# Deej.net
KiCad netlist of a schematic drawn in Altium Designer
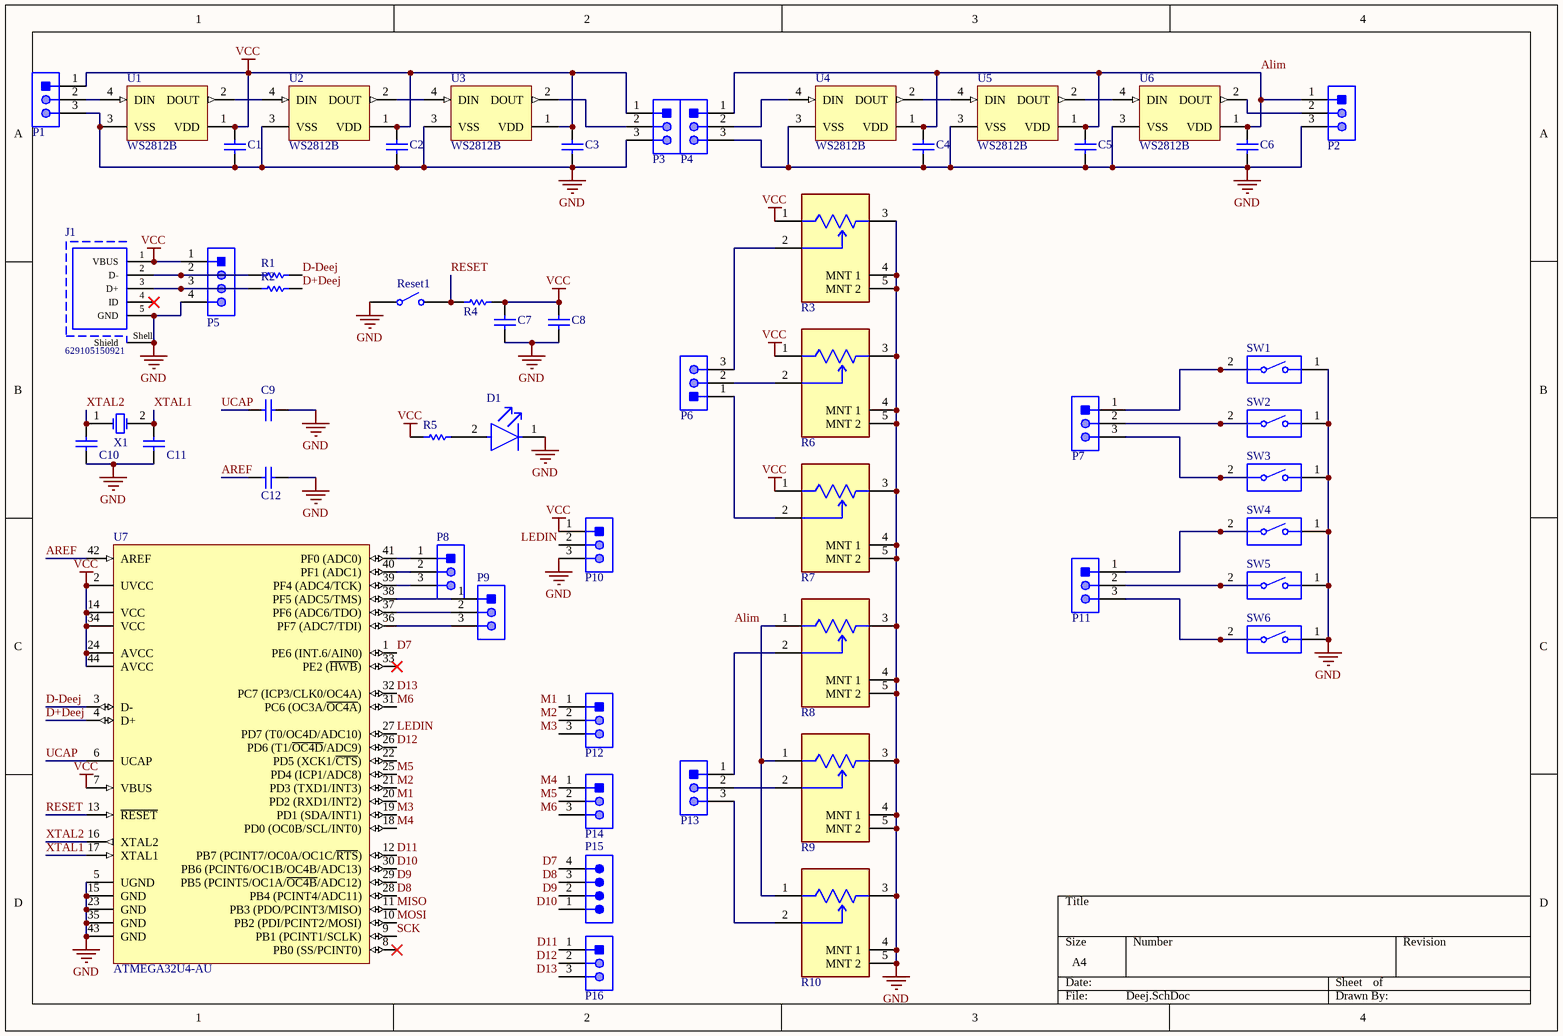
[diagram p0: Deej.SchDoc]

(export (version "E")
  (design (tool "Eeschema 10.0.6"))
  (components
    (comp (ref "C1")
      (value "GRM31C5C1E104JA01L")
      (footprint "CAPC3216X180X55LL20T25")
      (description "Chip Capacitor, 100 nF, +/- 5%, 25 V, -55 to 125 degC, 1206 (3216 Metric), RoHS, Tape and Reel")
      (fields (field (name "MANUFACTURER") "Murata"))
      (libsource (lib "Altium Content Vault") (part "CAP-NP-2"))
    )
    (comp (ref "C2")
      (value "GRM31C5C1E104JA01L")
      (footprint "CAPC3216X180X55LL20T25")
      (description "Chip Capacitor, 100 nF, +/- 5%, 25 V, -55 to 125 degC, 1206 (3216 Metric), RoHS, Tape and Reel")
      (fields (field (name "MANUFACTURER") "Murata"))
      (libsource (lib "Altium Content Vault") (part "CAP-NP-2"))
    )
    (comp (ref "C3")
      (value "GRM31C5C1E104JA01L")
      (footprint "CAPC3216X180X55LL20T25")
      (description "Chip Capacitor, 100 nF, +/- 5%, 25 V, -55 to 125 degC, 1206 (3216 Metric), RoHS, Tape and Reel")
      (fields (field (name "MANUFACTURER") "Murata"))
      (libsource (lib "Altium Content Vault") (part "CAP-NP-2"))
    )
    (comp (ref "C4")
      (value "GRM31C5C1E104JA01L")
      (footprint "CAPC3216X180X55LL20T25")
      (description "Chip Capacitor, 100 nF, +/- 5%, 25 V, -55 to 125 degC, 1206 (3216 Metric), RoHS, Tape and Reel")
      (fields (field (name "MANUFACTURER") "Murata"))
      (libsource (lib "Altium Content Vault") (part "CAP-NP-2"))
    )
    (comp (ref "C5")
      (value "GRM31C5C1E104JA01L")
      (footprint "CAPC3216X180X55LL20T25")
      (description "Chip Capacitor, 100 nF, +/- 5%, 25 V, -55 to 125 degC, 1206 (3216 Metric), RoHS, Tape and Reel")
      (fields (field (name "MANUFACTURER") "Murata"))
      (libsource (lib "Altium Content Vault") (part "CAP-NP-2"))
    )
    (comp (ref "C6")
      (value "GRM31C5C1E104JA01L")
      (footprint "CAPC3216X180X55LL20T25")
      (description "Chip Capacitor, 100 nF, +/- 5%, 25 V, -55 to 125 degC, 1206 (3216 Metric), RoHS, Tape and Reel")
      (fields (field (name "MANUFACTURER") "Murata"))
      (libsource (lib "Altium Content Vault") (part "CAP-NP-2"))
    )
    (comp (ref "C7")
      (value "GRM31C5C1E104JA01L")
      (footprint "CAPC3216X180X55LL20T25")
      (description "Chip Capacitor, 100 nF, +/- 5%, 25 V, -55 to 125 degC, 1206 (3216 Metric), RoHS, Tape and Reel")
      (fields (field (name "MANUFACTURER") "Murata"))
      (libsource (lib "Altium Content Vault") (part "CAP-NP-2"))
    )
    (comp (ref "C8")
      (value "GRM31C5C1E104JA01L")
      (footprint "CAPC3216X180X55LL20T25")
      (description "Chip Capacitor, 100 nF, +/- 5%, 25 V, -55 to 125 degC, 1206 (3216 Metric), RoHS, Tape and Reel")
      (fields (field (name "MANUFACTURER") "Murata"))
      (libsource (lib "Altium Content Vault") (part "CAP-NP-2"))
    )
    (comp (ref "C9")
      (value "C1206C105K3RACTU")
      (footprint "CAPC3216X180X50ML20T25")
      (description "Chip Capacitor, 1 uF, +/- 10%, 25 V, -55 to 125 degC, 1206 (3216 Metric), RoHS, Tape and Reel")
      (fields (field (name "MANUFACTURER") "Kemet") (field (name "TOLERANCE") "10%"))
      (libsource (lib "Altium Content Vault") (part "CAP-NP-2"))
    )
    (comp (ref "C10")
      (value "CAP 22pF 50V 1206(3216)")
      (footprint "CAPC1206(3216)100_N")
      (description "CAP 22nF 50V ±5% 1206 (3216 Metric) Thickness 1mm SMD")
      (fields (field (name "TOLERANCE") "Â±5%"))
      (libsource (lib "Altium Content Vault") (part "CAP"))
    )
    (comp (ref "C11")
      (value "CAP 22 pF 50V 1206(3216)")
      (footprint "CAPC1206(3216)100_N")
      (description "CAP 22nF 50V ±5% 1206 (3216 Metric) Thickness 1mm SMD")
      (fields (field (name "TOLERANCE") "Â±5%"))
      (libsource (lib "Altium Content Vault") (part "CAP"))
    )
    (comp (ref "C12")
      (value "GRM31C5C1E104JA01L")
      (footprint "CAPC3216X180X55LL20T25")
      (description "Chip Capacitor, 100 nF, +/- 5%, 25 V, -55 to 125 degC, 1206 (3216 Metric), RoHS, Tape and Reel")
      (fields (field (name "MANUFACTURER") "Murata"))
      (libsource (lib "Altium Content Vault") (part "CAP-NP-2"))
    )
    (comp (ref "D1")
      (value "APTD3216CGCK")
      (footprint "FP-APTD3216CGCK-MFG")
      (description "LED GREEN CLEAR 2SMD")
      (libsource (lib "Altium Content Vault") (part "8706943c75ba83719d021d2fdc84c58"))
    )
    (comp (ref "J1")
      (value "629105150921")
      (footprint "629105150921")
      (description "Micro USB 2.0 Type AB Receptacle WR-COM, Horizontal, SMT")
      (fields (field (name "MANUFACTURER") "Wurth Elektronik") (field (name "PUBLISHER") "WurthElektronik"))
      (libsource (lib "Altium Content Vault") (part "WE-USB-5-1SHLD"))
    )
    (comp (ref "P1")
      (value "22-28-4033")
      (footprint "MOLX-22-28-4033_V")
      (description "Male Header, Pitch 2.54 mm, 1 x 3 Position, Height 8.38 mm, Tail Length 3.18 mm, RoHS, Bulk")
      (fields (field (name "MANUFACTURER") "Molex"))
      (libsource (lib "") (part "CN-1P-M-R3_2"))
    )
    (comp (ref "P2")
      (value "22-28-4033")
      (footprint "MOLX-22-28-4033_V")
      (description "Male Header, Pitch 2.54 mm, 1 x 3 Position, Height 8.38 mm, Tail Length 3.18 mm, RoHS, Bulk")
      (fields (field (name "MANUFACTURER") "Molex"))
      (libsource (lib "Altium Content Vault") (part "CN-1P-M-R3"))
    )
    (comp (ref "P3")
      (value "22-28-4033")
      (footprint "MOLX-22-28-4033_V")
      (description "Male Header, Pitch 2.54 mm, 1 x 3 Position, Height 8.38 mm, Tail Length 3.18 mm, RoHS, Bulk")
      (fields (field (name "MANUFACTURER") "Molex"))
      (libsource (lib "Altium Content Vault") (part "CN-1P-M-R3"))
    )
    (comp (ref "P4")
      (value "22-28-4033")
      (footprint "MOLX-22-28-4033_V")
      (description "Male Header, Pitch 2.54 mm, 1 x 3 Position, Height 8.38 mm, Tail Length 3.18 mm, RoHS, Bulk")
      (fields (field (name "MANUFACTURER") "Molex"))
      (libsource (lib "") (part "CN-1P-M-R3_2"))
    )
    (comp (ref "P5")
      (value "61300411121")
      (footprint "61300411121")
      (description "THT Vertical Pin Header WR-PHD, Pitch 2.54 mm, Single Row, 4 pins")
      (fields (field (name "MANUFACTURER") "Wurth Elektronik") (field (name "PUBLISHER") "WurthElektronik"))
      (libsource (lib "Altium Content Vault") (part "WE-CN-1P-M-R4"))
    )
    (comp (ref "P6")
      (value "22-28-4033")
      (footprint "MOLX-22-28-4033_V")
      (description "Male Header, Pitch 2.54 mm, 1 x 3 Position, Height 8.38 mm, Tail Length 3.18 mm, RoHS, Bulk")
      (fields (field (name "MANUFACTURER") "Molex"))
      (libsource (lib "") (part "CN-1P-M-R3_1"))
    )
    (comp (ref "P7")
      (value "22-28-4033")
      (footprint "MOLX-22-28-4033_V")
      (description "Male Header, Pitch 2.54 mm, 1 x 3 Position, Height 8.38 mm, Tail Length 3.18 mm, RoHS, Bulk")
      (fields (field (name "MANUFACTURER") "Molex"))
      (libsource (lib "") (part "CN-1P-M-R3_2"))
    )
    (comp (ref "P8")
      (value "22-28-4033")
      (footprint "MOLX-22-28-4033_V")
      (description "Male Header, Pitch 2.54 mm, 1 x 3 Position, Height 8.38 mm, Tail Length 3.18 mm, RoHS, Bulk")
      (fields (field (name "MANUFACTURER") "Molex"))
      (libsource (lib "Altium Content Vault") (part "CN-1P-M-R3"))
    )
    (comp (ref "P9")
      (value "22-28-4033")
      (footprint "MOLX-22-28-4033_V")
      (description "Male Header, Pitch 2.54 mm, 1 x 3 Position, Height 8.38 mm, Tail Length 3.18 mm, RoHS, Bulk")
      (fields (field (name "MANUFACTURER") "Molex"))
      (libsource (lib "Altium Content Vault") (part "CN-1P-M-R3"))
    )
    (comp (ref "P10")
      (value "22-28-4033")
      (footprint "MOLX-22-28-4033_V")
      (description "Male Header, Pitch 2.54 mm, 1 x 3 Position, Height 8.38 mm, Tail Length 3.18 mm, RoHS, Bulk")
      (fields (field (name "MANUFACTURER") "Molex"))
      (libsource (lib "Altium Content Vault") (part "CN-1P-M-R3"))
    )
    (comp (ref "P11")
      (value "22-28-4033")
      (footprint "MOLX-22-28-4033_V")
      (description "Male Header, Pitch 2.54 mm, 1 x 3 Position, Height 8.38 mm, Tail Length 3.18 mm, RoHS, Bulk")
      (fields (field (name "MANUFACTURER") "Molex"))
      (libsource (lib "") (part "CN-1P-M-R3_2"))
    )
    (comp (ref "P12")
      (value "22-28-4033")
      (footprint "MOLX-22-28-4033_V")
      (description "Male Header, Pitch 2.54 mm, 1 x 3 Position, Height 8.38 mm, Tail Length 3.18 mm, RoHS, Bulk")
      (fields (field (name "MANUFACTURER") "Molex"))
      (libsource (lib "Altium Content Vault") (part "CN-1P-M-R3"))
    )
    (comp (ref "P13")
      (value "22-28-4033")
      (footprint "MOLX-22-28-4033_V")
      (description "Male Header, Pitch 2.54 mm, 1 x 3 Position, Height 8.38 mm, Tail Length 3.18 mm, RoHS, Bulk")
      (fields (field (name "MANUFACTURER") "Molex"))
      (libsource (lib "") (part "CN-1P-M-R3_2"))
    )
    (comp (ref "P14")
      (value "22-28-4033")
      (footprint "MOLX-22-28-4033_V")
      (description "Male Header, Pitch 2.54 mm, 1 x 3 Position, Height 8.38 mm, Tail Length 3.18 mm, RoHS, Bulk")
      (fields (field (name "MANUFACTURER") "Molex"))
      (libsource (lib "Altium Content Vault") (part "CN-1P-M-R3"))
    )
    (comp (ref "P15")
      (value "TSW-104-08-T-S")
      (footprint "SMTC-TSW-104-08-X-S")
      (description "0.025\" SQ Post Header, Through-hole, Vertical, -55 to 105 degC, 2.54 mm Pitch, 4-Pin, Male, RoHS")
      (fields (field (name "MANUFACTURER") "Samtec"))
      (libsource (lib "Altium Content Vault") (part "SMTC-TSW-104-08-X-S"))
    )
    (comp (ref "P16")
      (value "22-28-4033")
      (footprint "MOLX-22-28-4033_V")
      (description "Male Header, Pitch 2.54 mm, 1 x 3 Position, Height 8.38 mm, Tail Length 3.18 mm, RoHS, Bulk")
      (fields (field (name "MANUFACTURER") "Molex"))
      (libsource (lib "Altium Content Vault") (part "CN-1P-M-R3"))
    )
    (comp (ref "R1")
      (value "ERJ-8GEYJ220V")
      (footprint "RESC3216X70X50NL05T20")
      (fields (field (name "MANUFACTURER") "Panasonic"))
      (libsource (lib "Altium Content Vault") (part "RES"))
    )
    (comp (ref "R2")
      (value "ERJ-8GEYJ220V")
      (footprint "RESC3216X70X50NL05T20")
      (fields (field (name "MANUFACTURER") "Panasonic"))
      (libsource (lib "Altium Content Vault") (part "RES"))
    )
    (comp (ref "R3")
      (value "PTV09A-4020U-B103")
      (footprint "FP-PTV09A-4-MFG")
      (description "POT 10K OHM 1/20W CARBON LINEAR")
      (fields (field (name "TOLERANCE") "20%") (field (name "MANUFACTURER") "Bourns Inc."))
      (libsource (lib "Altium Content Vault") (part "3454c451b146ec4d4239c7813666f62"))
    )
    (comp (ref "R4")
      (value "ERJ-P08J103V")
      (footprint "RESC3216X70X50LL05T20")
      (fields (field (name "MANUFACTURER") "Panasonic"))
      (libsource (lib "Altium Content Vault") (part "RES"))
    )
    (comp (ref "R5")
      (value "ERJ8ENF2203V")
      (footprint "RESC3216X70X50LL05T20")
      (fields (field (name "MANUFACTURER") "Panasonic"))
      (libsource (lib "Altium Content Vault") (part "RES"))
    )
    (comp (ref "R6")
      (value "PTV09A-4020U-B103")
      (footprint "FP-PTV09A-4-MFG")
      (description "POT 10K OHM 1/20W CARBON LINEAR")
      (fields (field (name "TOLERANCE") "20%") (field (name "MANUFACTURER") "Bourns Inc."))
      (libsource (lib "Altium Content Vault") (part "3454c451b146ec4d4239c7813666f62"))
    )
    (comp (ref "R7")
      (value "PTV09A-4020U-B103")
      (footprint "FP-PTV09A-4-MFG")
      (description "POT 10K OHM 1/20W CARBON LINEAR")
      (fields (field (name "TOLERANCE") "20%") (field (name "MANUFACTURER") "Bourns Inc."))
      (libsource (lib "Altium Content Vault") (part "3454c451b146ec4d4239c7813666f62"))
    )
    (comp (ref "R8")
      (value "PTV09A-4020U-B103")
      (footprint "FP-PTV09A-4-MFG")
      (description "POT 10K OHM 1/20W CARBON LINEAR")
      (fields (field (name "TOLERANCE") "20%") (field (name "MANUFACTURER") "Bourns Inc."))
      (libsource (lib "Altium Content Vault") (part "3454c451b146ec4d4239c7813666f62"))
    )
    (comp (ref "R9")
      (value "PTV09A-4020U-B103")
      (footprint "FP-PTV09A-4-MFG")
      (description "POT 10K OHM 1/20W CARBON LINEAR")
      (fields (field (name "TOLERANCE") "20%") (field (name "MANUFACTURER") "Bourns Inc."))
      (libsource (lib "Altium Content Vault") (part "3454c451b146ec4d4239c7813666f62"))
    )
    (comp (ref "R10")
      (value "PTV09A-4020U-B103")
      (footprint "FP-PTV09A-4-MFG")
      (description "POT 10K OHM 1/20W CARBON LINEAR")
      (fields (field (name "TOLERANCE") "20%") (field (name "MANUFACTURER") "Bourns Inc."))
      (libsource (lib "Altium Content Vault") (part "3454c451b146ec4d4239c7813666f62"))
    )
    (comp (ref "Reset1")
      (value "434121025816")
      (footprint "434121025816")
      (description "WS-TASV SMD Tact Switch 6.0X3.8 mm")
      (fields (field (name "MANUFACTURER") "Wuerth Elektronik"))
      (libsource (lib "Altium Content Vault") (part "WE-TACT-SW-2"))
    )
    (comp (ref "SW1")
      (value "MX1A-11NW")
      (footprint "CHRY-MX1A-11NW_V")
      (description "Keylock Switch, 12 V, -10 to 70 degC, 2-Pin THD, RoHS, Bulk")
      (fields (field (name "MANUFACTURER") "Cherry") (field (name "PART NO") "MX1A11NW"))
      (libsource (lib "Altium Content Vault") (part "KEYSW-SPST-2"))
    )
    (comp (ref "SW2")
      (value "MX1A-11NW")
      (footprint "CHRY-MX1A-11NW_V")
      (description "Keylock Switch, 12 V, -10 to 70 degC, 2-Pin THD, RoHS, Bulk")
      (fields (field (name "MANUFACTURER") "Cherry") (field (name "PART NO") "MX1A11NW"))
      (libsource (lib "Altium Content Vault") (part "KEYSW-SPST-2"))
    )
    (comp (ref "SW3")
      (value "MX1A-11NW")
      (footprint "CHRY-MX1A-11NW_V")
      (description "Keylock Switch, 12 V, -10 to 70 degC, 2-Pin THD, RoHS, Bulk")
      (fields (field (name "MANUFACTURER") "Cherry") (field (name "PART NO") "MX1A11NW"))
      (libsource (lib "Altium Content Vault") (part "KEYSW-SPST-2"))
    )
    (comp (ref "SW4")
      (value "MX1A-11NW")
      (footprint "CHRY-MX1A-11NW_V")
      (description "Keylock Switch, 12 V, -10 to 70 degC, 2-Pin THD, RoHS, Bulk")
      (fields (field (name "MANUFACTURER") "Cherry") (field (name "PART NO") "MX1A11NW"))
      (libsource (lib "Altium Content Vault") (part "KEYSW-SPST-2"))
    )
    (comp (ref "SW5")
      (value "MX1A-11NW")
      (footprint "CHRY-MX1A-11NW_V")
      (description "Keylock Switch, 12 V, -10 to 70 degC, 2-Pin THD, RoHS, Bulk")
      (fields (field (name "MANUFACTURER") "Cherry") (field (name "PART NO") "MX1A11NW"))
      (libsource (lib "Altium Content Vault") (part "KEYSW-SPST-2"))
    )
    (comp (ref "SW6")
      (value "MX1A-11NW")
      (footprint "CHRY-MX1A-11NW_V")
      (description "Keylock Switch, 12 V, -10 to 70 degC, 2-Pin THD, RoHS, Bulk")
      (fields (field (name "MANUFACTURER") "Cherry") (field (name "PART NO") "MX1A11NW"))
      (libsource (lib "Altium Content Vault") (part "KEYSW-SPST-2"))
    )
    (comp (ref "U1")
      (value "WS2812B")
      (footprint "ADAI-WS2812B_V")
      (fields (field (name "MANUFACTURER") "Adafruit Industries"))
      (libsource (lib "Le Niniven Thomas") (part "ADAI-WS2812B-4"))
    )
    (comp (ref "U2")
      (value "WS2812B")
      (footprint "ADAI-WS2812B_V")
      (fields (field (name "MANUFACTURER") "Adafruit Industries"))
      (libsource (lib "Le Niniven Thomas") (part "ADAI-WS2812B-4"))
    )
    (comp (ref "U3")
      (value "WS2812B")
      (footprint "ADAI-WS2812B_V")
      (fields (field (name "MANUFACTURER") "Adafruit Industries"))
      (libsource (lib "Le Niniven Thomas") (part "ADAI-WS2812B-4"))
    )
    (comp (ref "U4")
      (value "WS2812B")
      (footprint "ADAI-WS2812B_V")
      (fields (field (name "MANUFACTURER") "Adafruit Industries"))
      (libsource (lib "Le Niniven Thomas") (part "ADAI-WS2812B-4"))
    )
    (comp (ref "U5")
      (value "WS2812B")
      (footprint "ADAI-WS2812B_V")
      (fields (field (name "MANUFACTURER") "Adafruit Industries"))
      (libsource (lib "Le Niniven Thomas") (part "ADAI-WS2812B-4"))
    )
    (comp (ref "U6")
      (value "WS2812B")
      (footprint "ADAI-WS2812B_V")
      (fields (field (name "MANUFACTURER") "Adafruit Industries"))
      (libsource (lib "Le Niniven Thomas") (part "ADAI-WS2812B-4"))
    )
    (comp (ref "U7")
      (value "ATMEGA32U4-AU")
      (footprint "ATML-44ML_M")
      (fields (field (name "MANUFACTURER") "Atmel"))
      (libsource (lib "Le Niniven Thomas") (part "MC-8B-ATM16U4-SQ44"))
    )
    (comp (ref "X1")
      (value "9C-3.6864MBBK-T")
      (footprint "TXC-9C-2_V")
      (fields (field (name "MANUFACTURER") "TXC"))
      (libsource (lib "Altium Content Vault") (part "TXC-XTAL_1-2-2"))
    )
  )
  (nets
    (net (code "1") (name "/AREF") (class "Default")
      (node (ref "C12") (pin "2") (pinfunction "2_2") (pintype "passive"))
      (node (ref "U7") (pin "42") (pinfunction "AREF_42") (pintype "input"))
    )
    (net (code "2") (name "/Alim") (class "Default")
      (node (ref "C4") (pin "2") (pinfunction "2_2") (pintype "passive"))
      (node (ref "C5") (pin "2") (pinfunction "2_2") (pintype "passive"))
      (node (ref "C6") (pin "2") (pinfunction "2_2") (pintype "passive"))
      (node (ref "P2") (pin "1") (pinfunction "1_1") (pintype "passive"))
      (node (ref "P4") (pin "1") (pinfunction "1_1") (pintype "passive"))
      (node (ref "R10") (pin "1") (pinfunction "1_1") (pintype "passive"))
      (node (ref "R8") (pin "1") (pinfunction "1_1") (pintype "passive"))
      (node (ref "R9") (pin "1") (pinfunction "1_1") (pintype "passive"))
      (node (ref "U4") (pin "1") (pinfunction "VDD_1") (pintype "power_in"))
      (node (ref "U5") (pin "1") (pinfunction "VDD_1") (pintype "power_in"))
      (node (ref "U6") (pin "1") (pinfunction "VDD_1") (pintype "power_in"))
    )
    (net (code "3") (name "/D+Deej") (class "Default")
      (node (ref "R2") (pin "2") (pinfunction "2_2") (pintype "passive"))
      (node (ref "U7") (pin "4") (pinfunction "D+_4") (pintype "bidirectional"))
    )
    (net (code "4") (name "/D-Deej") (class "Default")
      (node (ref "R1") (pin "2") (pinfunction "2_2") (pintype "passive"))
      (node (ref "U7") (pin "3") (pinfunction "D-_3") (pintype "bidirectional"))
    )
    (net (code "5") (name "/D7") (class "Default")
      (node (ref "P15") (pin "4") (pinfunction "4_4") (pintype "passive"))
      (node (ref "U7") (pin "1") (pinfunction "PE6_(INT.6/AIN0)_1") (pintype "bidirectional"))
    )
    (net (code "6") (name "/D8") (class "Default")
      (node (ref "P15") (pin "3") (pinfunction "3_3") (pintype "passive"))
      (node (ref "U7") (pin "28") (pinfunction "PB4_(PCINT4/ADC11)_28") (pintype "bidirectional"))
    )
    (net (code "7") (name "/D9") (class "Default")
      (node (ref "P15") (pin "2") (pinfunction "2_2") (pintype "passive"))
      (node (ref "U7") (pin "29") (pinfunction "PB5_(PCINT5/OC1A/~{OC4B}/ADC12)_29") (pintype "bidirectional"))
    )
    (net (code "8") (name "/D10") (class "Default")
      (node (ref "P15") (pin "1") (pinfunction "1_1") (pintype "passive"))
      (node (ref "U7") (pin "30") (pinfunction "PB6_(PCINT6/OC1B/OC4B/ADC13)_30") (pintype "bidirectional"))
    )
    (net (code "9") (name "/D11") (class "Default")
      (node (ref "P16") (pin "1") (pinfunction "1_1") (pintype "passive"))
      (node (ref "U7") (pin "12") (pinfunction "PB7_(PCINT7/OC0A/OC1C/~{RTS})_12") (pintype "bidirectional"))
    )
    (net (code "10") (name "/D12") (class "Default")
      (node (ref "P16") (pin "2") (pinfunction "2_2") (pintype "passive"))
      (node (ref "U7") (pin "26") (pinfunction "PD6_(T1/~{OC4D}/ADC9)_26") (pintype "bidirectional"))
    )
    (net (code "11") (name "/D13") (class "Default")
      (node (ref "P16") (pin "3") (pinfunction "3_3") (pintype "passive"))
      (node (ref "U7") (pin "32") (pinfunction "PC7_(ICP3/CLK0/OC4A)_32") (pintype "bidirectional"))
    )
    (net (code "12") (name "/LEDIN") (class "Default")
      (node (ref "P10") (pin "2") (pinfunction "2_2") (pintype "passive"))
      (node (ref "U7") (pin "27") (pinfunction "PD7_(T0/OC4D/ADC10)_27") (pintype "bidirectional"))
    )
    (net (code "13") (name "/M1") (class "Default")
      (node (ref "P12") (pin "1") (pinfunction "1_1") (pintype "passive"))
      (node (ref "U7") (pin "20") (pinfunction "PD2_(RXD1/INT2)_20") (pintype "bidirectional"))
    )
    (net (code "14") (name "/M2") (class "Default")
      (node (ref "P12") (pin "2") (pinfunction "2_2") (pintype "passive"))
      (node (ref "U7") (pin "21") (pinfunction "PD3_(TXD1/INT3)_21") (pintype "bidirectional"))
    )
    (net (code "15") (name "/M3") (class "Default")
      (node (ref "P12") (pin "3") (pinfunction "3_3") (pintype "passive"))
      (node (ref "U7") (pin "19") (pinfunction "PD1_(SDA/INT1)_19") (pintype "bidirectional"))
    )
    (net (code "16") (name "/M4") (class "Default")
      (node (ref "P14") (pin "1") (pinfunction "1_1") (pintype "passive"))
      (node (ref "U7") (pin "18") (pinfunction "PD0_(OC0B/SCL/INT0)_18") (pintype "bidirectional"))
    )
    (net (code "17") (name "/M5") (class "Default")
      (node (ref "P14") (pin "2") (pinfunction "2_2") (pintype "passive"))
      (node (ref "U7") (pin "25") (pinfunction "PD4_(ICP1/ADC8)_25") (pintype "bidirectional"))
    )
    (net (code "18") (name "/M6") (class "Default")
      (node (ref "P14") (pin "3") (pinfunction "3_3") (pintype "passive"))
      (node (ref "U7") (pin "31") (pinfunction "PC6_(OC3A/~{OC4A})_31") (pintype "bidirectional"))
    )
    (net (code "19") (name "/MISO") (class "Default")
      (node (ref "U7") (pin "11") (pinfunction "PB3_(PDO/PCINT3/MISO)_11") (pintype "bidirectional"))
    )
    (net (code "20") (name "/MOSI") (class "Default")
      (node (ref "U7") (pin "10") (pinfunction "PB2_(PDI/PCINT2/MOSI)_10") (pintype "bidirectional"))
    )
    (net (code "21") (name "/RESET") (class "Default")
      (node (ref "R4") (pin "2") (pinfunction "2_2") (pintype "passive"))
      (node (ref "Reset1") (pin "2") (pinfunction "2_2") (pintype "passive"))
      (node (ref "U7") (pin "13") (pinfunction "~{RESET}_13") (pintype "input"))
    )
    (net (code "22") (name "/SCK") (class "Default")
      (node (ref "U7") (pin "9") (pinfunction "PB1_(PCINT1/SCLK)_9") (pintype "bidirectional"))
    )
    (net (code "23") (name "/UCAP") (class "Default")
      (node (ref "C9") (pin "1") (pinfunction "1_1") (pintype "passive"))
      (node (ref "U7") (pin "6") (pinfunction "UCAP_6") (pintype "passive"))
    )
    (net (code "24") (name "/XTAL1") (class "Default")
      (node (ref "C11") (pin "2") (pinfunction "2_2") (pintype "passive"))
      (node (ref "U7") (pin "17") (pinfunction "XTAL1_17") (pintype "input"))
      (node (ref "X1") (pin "2") (pinfunction "X2_2") (pintype "passive"))
    )
    (net (code "25") (name "/XTAL2") (class "Default")
      (node (ref "C10") (pin "2") (pinfunction "2_2") (pintype "passive"))
      (node (ref "U7") (pin "16") (pinfunction "XTAL2_16") (pintype "output"))
      (node (ref "X1") (pin "1") (pinfunction "X1_1") (pintype "passive"))
    )
    (net (code "26") (name "GND") (class "Default")
      (node (ref "C1") (pin "1") (pinfunction "1_1") (pintype "passive"))
      (node (ref "C10") (pin "1") (pinfunction "1_1") (pintype "passive"))
      (node (ref "C11") (pin "1") (pinfunction "1_1") (pintype "passive"))
      (node (ref "C12") (pin "1") (pinfunction "1_1") (pintype "passive"))
      (node (ref "C2") (pin "1") (pinfunction "1_1") (pintype "passive"))
      (node (ref "C3") (pin "1") (pinfunction "1_1") (pintype "passive"))
      (node (ref "C4") (pin "1") (pinfunction "1_1") (pintype "passive"))
      (node (ref "C5") (pin "1") (pinfunction "1_1") (pintype "passive"))
      (node (ref "C6") (pin "1") (pinfunction "1_1") (pintype "passive"))
      (node (ref "C7") (pin "1") (pinfunction "1_1") (pintype "passive"))
      (node (ref "C8") (pin "1") (pinfunction "1_1") (pintype "passive"))
      (node (ref "C9") (pin "2") (pinfunction "2_2") (pintype "passive"))
      (node (ref "D1") (pin "1") (pinfunction "C_1") (pintype "passive"))
      (node (ref "J1") (pin "5") (pinfunction "GND_5") (pintype "passive"))
      (node (ref "J1") (pin "Shell") (pinfunction "Shield_Shell") (pintype "passive"))
      (node (ref "P1") (pin "3") (pinfunction "3_3") (pintype "passive"))
      (node (ref "P10") (pin "3") (pinfunction "3_3") (pintype "passive"))
      (node (ref "P2") (pin "3") (pinfunction "3_3") (pintype "passive"))
      (node (ref "P3") (pin "3") (pinfunction "3_3") (pintype "passive"))
      (node (ref "P4") (pin "3") (pinfunction "3_3") (pintype "passive"))
      (node (ref "P5") (pin "4") (pinfunction "4_4") (pintype "passive"))
      (node (ref "R10") (pin "3") (pinfunction "3_3") (pintype "passive"))
      (node (ref "R10") (pin "4") (pinfunction "MNT_1_4") (pintype "passive"))
      (node (ref "R10") (pin "5") (pinfunction "MNT_2_5") (pintype "passive"))
      (node (ref "R3") (pin "3") (pinfunction "3_3") (pintype "passive"))
      (node (ref "R3") (pin "4") (pinfunction "MNT_1_4") (pintype "passive"))
      (node (ref "R3") (pin "5") (pinfunction "MNT_2_5") (pintype "passive"))
      (node (ref "R6") (pin "3") (pinfunction "3_3") (pintype "passive"))
      (node (ref "R6") (pin "4") (pinfunction "MNT_1_4") (pintype "passive"))
      (node (ref "R6") (pin "5") (pinfunction "MNT_2_5") (pintype "passive"))
      (node (ref "R7") (pin "3") (pinfunction "3_3") (pintype "passive"))
      (node (ref "R7") (pin "4") (pinfunction "MNT_1_4") (pintype "passive"))
      (node (ref "R7") (pin "5") (pinfunction "MNT_2_5") (pintype "passive"))
      (node (ref "R8") (pin "3") (pinfunction "3_3") (pintype "passive"))
      (node (ref "R8") (pin "4") (pinfunction "MNT_1_4") (pintype "passive"))
      (node (ref "R8") (pin "5") (pinfunction "MNT_2_5") (pintype "passive"))
      (node (ref "R9") (pin "3") (pinfunction "3_3") (pintype "passive"))
      (node (ref "R9") (pin "4") (pinfunction "MNT_1_4") (pintype "passive"))
      (node (ref "R9") (pin "5") (pinfunction "MNT_2_5") (pintype "passive"))
      (node (ref "Reset1") (pin "1") (pinfunction "1_1") (pintype "passive"))
      (node (ref "SW1") (pin "1") (pinfunction "1_1") (pintype "passive"))
      (node (ref "SW2") (pin "1") (pinfunction "1_1") (pintype "passive"))
      (node (ref "SW3") (pin "1") (pinfunction "1_1") (pintype "passive"))
      (node (ref "SW4") (pin "1") (pinfunction "1_1") (pintype "passive"))
      (node (ref "SW5") (pin "1") (pinfunction "1_1") (pintype "passive"))
      (node (ref "SW6") (pin "1") (pinfunction "1_1") (pintype "passive"))
      (node (ref "U1") (pin "3") (pinfunction "VSS_3") (pintype "power_in"))
      (node (ref "U2") (pin "3") (pinfunction "VSS_3") (pintype "power_in"))
      (node (ref "U3") (pin "3") (pinfunction "VSS_3") (pintype "power_in"))
      (node (ref "U4") (pin "3") (pinfunction "VSS_3") (pintype "power_in"))
      (node (ref "U5") (pin "3") (pinfunction "VSS_3") (pintype "power_in"))
      (node (ref "U6") (pin "3") (pinfunction "VSS_3") (pintype "power_in"))
      (node (ref "U7") (pin "15") (pinfunction "GND_15") (pintype "power_in"))
      (node (ref "U7") (pin "23") (pinfunction "GND_23") (pintype "power_in"))
      (node (ref "U7") (pin "35") (pinfunction "GND_35") (pintype "power_in"))
      (node (ref "U7") (pin "43") (pinfunction "GND_43") (pintype "power_in"))
      (node (ref "U7") (pin "5") (pinfunction "UGND_5") (pintype "power_in"))
    )
    (net (code "27") (name "Net-(D1-A)") (class "Default")
      (node (ref "D1") (pin "2") (pinfunction "A_2") (pintype "passive"))
      (node (ref "R5") (pin "2") (pinfunction "2_2") (pintype "passive"))
    )
    (net (code "28") (name "Net-(J1-D+)") (class "Default")
      (node (ref "J1") (pin "3") (pinfunction "D+_3") (pintype "passive"))
      (node (ref "P5") (pin "3") (pinfunction "3_3") (pintype "passive"))
      (node (ref "R2") (pin "1") (pinfunction "1_1") (pintype "passive"))
    )
    (net (code "29") (name "Net-(J1-D-)") (class "Default")
      (node (ref "J1") (pin "2") (pinfunction "D-_2") (pintype "passive"))
      (node (ref "P5") (pin "2") (pinfunction "2_2") (pintype "passive"))
      (node (ref "R1") (pin "1") (pinfunction "1_1") (pintype "passive"))
    )
    (net (code "30") (name "Net-(P6-Pad1)") (class "Default")
      (node (ref "P6") (pin "1") (pinfunction "1_1") (pintype "passive"))
      (node (ref "R7") (pin "2") (pinfunction "2_2") (pintype "passive"))
    )
    (net (code "31") (name "Net-(P6-Pad2)") (class "Default")
      (node (ref "P6") (pin "2") (pinfunction "2_2") (pintype "passive"))
      (node (ref "R6") (pin "2") (pinfunction "2_2") (pintype "passive"))
    )
    (net (code "32") (name "Net-(P6-Pad3)") (class "Default")
      (node (ref "P6") (pin "3") (pinfunction "3_3") (pintype "passive"))
      (node (ref "R3") (pin "2") (pinfunction "2_2") (pintype "passive"))
    )
    (net (code "33") (name "Net-(P7-Pad1)") (class "Default")
      (node (ref "P7") (pin "1") (pinfunction "1_1") (pintype "passive"))
      (node (ref "SW1") (pin "2") (pinfunction "2_2") (pintype "passive"))
    )
    (net (code "34") (name "Net-(P7-Pad2)") (class "Default")
      (node (ref "P7") (pin "2") (pinfunction "2_2") (pintype "passive"))
      (node (ref "SW2") (pin "2") (pinfunction "2_2") (pintype "passive"))
    )
    (net (code "35") (name "Net-(P7-Pad3)") (class "Default")
      (node (ref "P7") (pin "3") (pinfunction "3_3") (pintype "passive"))
      (node (ref "SW3") (pin "2") (pinfunction "2_2") (pintype "passive"))
    )
    (net (code "36") (name "Net-(P11-Pad1)") (class "Default")
      (node (ref "P11") (pin "1") (pinfunction "1_1") (pintype "passive"))
      (node (ref "SW4") (pin "2") (pinfunction "2_2") (pintype "passive"))
    )
    (net (code "37") (name "Net-(P11-Pad2)") (class "Default")
      (node (ref "P11") (pin "2") (pinfunction "2_2") (pintype "passive"))
      (node (ref "SW5") (pin "2") (pinfunction "2_2") (pintype "passive"))
    )
    (net (code "38") (name "Net-(P11-Pad3)") (class "Default")
      (node (ref "P11") (pin "3") (pinfunction "3_3") (pintype "passive"))
      (node (ref "SW6") (pin "2") (pinfunction "2_2") (pintype "passive"))
    )
    (net (code "39") (name "Net-(P13-Pad1)") (class "Default")
      (node (ref "P13") (pin "1") (pinfunction "1_1") (pintype "passive"))
      (node (ref "R8") (pin "2") (pinfunction "2_2") (pintype "passive"))
    )
    (net (code "40") (name "Net-(P13-Pad2)") (class "Default")
      (node (ref "P13") (pin "2") (pinfunction "2_2") (pintype "passive"))
      (node (ref "R9") (pin "2") (pinfunction "2_2") (pintype "passive"))
    )
    (net (code "41") (name "Net-(P13-Pad3)") (class "Default")
      (node (ref "P13") (pin "3") (pinfunction "3_3") (pintype "passive"))
      (node (ref "R10") (pin "2") (pinfunction "2_2") (pintype "passive"))
    )
    (net (code "42") (name "Net-(U1-DIN)") (class "Default")
      (node (ref "P1") (pin "2") (pinfunction "2_2") (pintype "passive"))
      (node (ref "U1") (pin "4") (pinfunction "DIN_4") (pintype "input"))
    )
    (net (code "43") (name "Net-(U1-DOUT)") (class "Default")
      (node (ref "U1") (pin "2") (pinfunction "DOUT_2") (pintype "output"))
      (node (ref "U2") (pin "4") (pinfunction "DIN_4") (pintype "input"))
    )
    (net (code "44") (name "Net-(U2-DOUT)") (class "Default")
      (node (ref "U2") (pin "2") (pinfunction "DOUT_2") (pintype "output"))
      (node (ref "U3") (pin "4") (pinfunction "DIN_4") (pintype "input"))
    )
    (net (code "45") (name "Net-(U3-DOUT)") (class "Default")
      (node (ref "P3") (pin "2") (pinfunction "2_2") (pintype "passive"))
      (node (ref "U3") (pin "2") (pinfunction "DOUT_2") (pintype "output"))
    )
    (net (code "46") (name "Net-(U4-DIN)") (class "Default")
      (node (ref "P4") (pin "2") (pinfunction "2_2") (pintype "passive"))
      (node (ref "U4") (pin "4") (pinfunction "DIN_4") (pintype "input"))
    )
    (net (code "47") (name "Net-(U4-DOUT)") (class "Default")
      (node (ref "U4") (pin "2") (pinfunction "DOUT_2") (pintype "output"))
      (node (ref "U5") (pin "4") (pinfunction "DIN_4") (pintype "input"))
    )
    (net (code "48") (name "Net-(U5-DOUT)") (class "Default")
      (node (ref "U5") (pin "2") (pinfunction "DOUT_2") (pintype "output"))
      (node (ref "U6") (pin "4") (pinfunction "DIN_4") (pintype "input"))
    )
    (net (code "49") (name "Net-(U6-DOUT)") (class "Default")
      (node (ref "P2") (pin "2") (pinfunction "2_2") (pintype "passive"))
      (node (ref "U6") (pin "2") (pinfunction "DOUT_2") (pintype "output"))
    )
    (net (code "50") (name "Net-(U7-PF0_(ADC0))") (class "Default")
      (node (ref "P8") (pin "1") (pinfunction "1_1") (pintype "passive"))
      (node (ref "U7") (pin "41") (pinfunction "PF0_(ADC0)_41") (pintype "bidirectional"))
    )
    (net (code "51") (name "Net-(U7-PF1_(ADC1))") (class "Default")
      (node (ref "P8") (pin "2") (pinfunction "2_2") (pintype "passive"))
      (node (ref "U7") (pin "40") (pinfunction "PF1_(ADC1)_40") (pintype "bidirectional"))
    )
    (net (code "52") (name "Net-(U7-PF4_(ADC4{slash}TCK))") (class "Default")
      (node (ref "P8") (pin "3") (pinfunction "3_3") (pintype "passive"))
      (node (ref "U7") (pin "39") (pinfunction "PF4_(ADC4/TCK)_39") (pintype "bidirectional"))
    )
    (net (code "53") (name "Net-(U7-PF5_(ADC5{slash}TMS))") (class "Default")
      (node (ref "P9") (pin "1") (pinfunction "1_1") (pintype "passive"))
      (node (ref "U7") (pin "38") (pinfunction "PF5_(ADC5/TMS)_38") (pintype "bidirectional"))
    )
    (net (code "54") (name "Net-(U7-PF6_(ADC6{slash}TDO))") (class "Default")
      (node (ref "P9") (pin "2") (pinfunction "2_2") (pintype "passive"))
      (node (ref "U7") (pin "37") (pinfunction "PF6_(ADC6/TDO)_37") (pintype "bidirectional"))
    )
    (net (code "55") (name "Net-(U7-PF7_(ADC7{slash}TDI))") (class "Default")
      (node (ref "P9") (pin "3") (pinfunction "3_3") (pintype "passive"))
      (node (ref "U7") (pin "36") (pinfunction "PF7_(ADC7/TDI)_36") (pintype "bidirectional"))
    )
    (net (code "56") (name "VCC") (class "Default")
      (node (ref "C1") (pin "2") (pinfunction "2_2") (pintype "passive"))
      (node (ref "C2") (pin "2") (pinfunction "2_2") (pintype "passive"))
      (node (ref "C3") (pin "2") (pinfunction "2_2") (pintype "passive"))
      (node (ref "C7") (pin "2") (pinfunction "2_2") (pintype "passive"))
      (node (ref "C8") (pin "2") (pinfunction "2_2") (pintype "passive"))
      (node (ref "J1") (pin "1") (pinfunction "VBUS_1") (pintype "passive"))
      (node (ref "P1") (pin "1") (pinfunction "1_1") (pintype "passive"))
      (node (ref "P10") (pin "1") (pinfunction "1_1") (pintype "passive"))
      (node (ref "P3") (pin "1") (pinfunction "1_1") (pintype "passive"))
      (node (ref "P5") (pin "1") (pinfunction "1_1") (pintype "passive"))
      (node (ref "R3") (pin "1") (pinfunction "1_1") (pintype "passive"))
      (node (ref "R4") (pin "1") (pinfunction "1_1") (pintype "passive"))
      (node (ref "R5") (pin "1") (pinfunction "1_1") (pintype "passive"))
      (node (ref "R6") (pin "1") (pinfunction "1_1") (pintype "passive"))
      (node (ref "R7") (pin "1") (pinfunction "1_1") (pintype "passive"))
      (node (ref "U1") (pin "1") (pinfunction "VDD_1") (pintype "power_in"))
      (node (ref "U2") (pin "1") (pinfunction "VDD_1") (pintype "power_in"))
      (node (ref "U3") (pin "1") (pinfunction "VDD_1") (pintype "power_in"))
      (node (ref "U7") (pin "14") (pinfunction "VCC_14") (pintype "power_in"))
      (node (ref "U7") (pin "2") (pinfunction "UVCC_2") (pintype "power_in"))
      (node (ref "U7") (pin "24") (pinfunction "AVCC_24") (pintype "power_in"))
      (node (ref "U7") (pin "34") (pinfunction "VCC_34") (pintype "power_in"))
      (node (ref "U7") (pin "44") (pinfunction "AVCC_44") (pintype "power_in"))
      (node (ref "U7") (pin "7") (pinfunction "VBUS_7") (pintype "input"))
    )
    (net (code "57") (name "unconnected-(J1-ID-Pad4)") (class "Default")
      (node (ref "J1") (pin "4") (pinfunction "ID_4") (pintype "passive+no_connect"))
    )
    (net (code "58") (name "unconnected-(U7-PB0_(SS{slash}PCINT0)-Pad8)") (class "Default")
      (node (ref "U7") (pin "8") (pinfunction "PB0_(SS/PCINT0)_8") (pintype "bidirectional+no_connect"))
    )
    (net (code "59") (name "unconnected-(U7-PD5_(XCK1{slash}~{CTS})-Pad22)") (class "Default")
      (node (ref "U7") (pin "22") (pinfunction "PD5_(XCK1/~{CTS})_22") (pintype "bidirectional"))
    )
    (net (code "60") (name "unconnected-(U7-PE2_(~{HWB})-Pad33)") (class "Default")
      (node (ref "U7") (pin "33") (pinfunction "PE2_(~{HWB})_33") (pintype "bidirectional+no_connect"))
    )
  )
)
